# USB_UART.net
KiCad netlist of a schematic drawn in Altium Designer
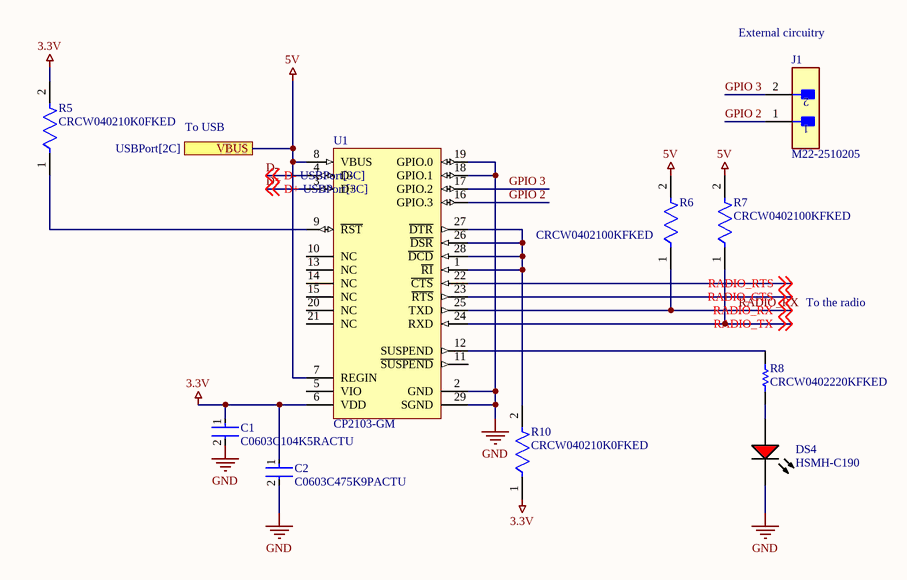
[diagram p0: USB_UART.SchDoc]

(export (version "E")
  (design (tool "Eeschema 10.0.6"))
  (components
    (comp (ref "C1")
      (value "C0603C104K5RACTU")
      (footprint "FP-C0603C-CF-MFG")
      (description "CAP CER 0.1UF 50V X7R 0603")
      (fields (field (name "TOLERANCE") "0.1") (field (name "MANUFACTURER") "KEMET"))
      (libsource (lib "Altium Content Vault") (part "b4654b650e69147ec39a6b967a45e02"))
    )
    (comp (ref "C2")
      (value "C0603C475K9PACTU")
      (footprint "FP-C0603-CG-MFG")
      (description "CAP CER 4.7UF 6.3V X5R 0603")
      (fields (field (name "TOLERANCE") "10%") (field (name "MANUFACTURER") "Kemet"))
      (libsource (lib "Altium Content Vault") (part "11868f565c42a9108669ba33697ecf6"))
    )
    (comp (ref "DS4")
      (value "HSMH-C190")
      (footprint "AVAG-HSMX-C190_V")
      (description "LED Uni-Color Red, 65 mW, 20 mA, -40 to 85 degC, 2-Pin SMD, RoHS, Tape and Reel")
      (libsource (lib "Altium Content Vault") (part "LED-RED-AK-2"))
    )
    (comp (ref "J1")
      (value "M22-2510205")
      (footprint "FP-M22-2510205-MFG")
      (description "CONN HEADER VERT 2POS 2MM")
      (fields
        (field (name "MANUFACTURER") "Harwin")
        (field (name "OCTOPART") "https://octopart.com/m22-2510205-harwin-2538221")
      )
      (libsource (lib "Altium Content Vault") (part "3bc925449376181038e59eaffc5286c"))
    )
    (comp (ref "R5")
      (value "CRCW040210K0FKED")
      (footprint "FP-CRCW0402-e3-IPC_B")
      (description "RES SMD 10K OHM 1% 1/16W 0402")
      (fields (field (name "TOLERANCE") "1%"))
      (libsource (lib "Altium Content Vault") (part "1029c3af85768c4190bb7ad29bc67b5"))
    )
    (comp (ref "R6")
      (value "CRCW0402100KFKED")
      (footprint "FP-CRCW0402-e3-IPC_C")
      (description "RES Thick Film, 100kΩ, 1%, 0.063W, 100ppm/°C, 0402")
      (fields (field (name "TOLERANCE") "1%"))
      (libsource (lib "Altium Content Vault") (part "1029c3af85768c4190bb7ad29bc67b5"))
    )
    (comp (ref "R7")
      (value "CRCW0402100KFKED")
      (footprint "FP-CRCW0402-e3-IPC_C")
      (description "RES Thick Film, 100kΩ, 1%, 0.063W, 100ppm/°C, 0402")
      (fields (field (name "TOLERANCE") "1%"))
      (libsource (lib "Altium Content Vault") (part "1029c3af85768c4190bb7ad29bc67b5"))
    )
    (comp (ref "R8")
      (value "CRCW0402220KFKED")
      (footprint "RESC1005X40X25LL05T05")
      (fields (field (name "MANUFACTURER") "Vishay Dale"))
      (libsource (lib "Altium Content Vault") (part "RES"))
    )
    (comp (ref "R10")
      (value "CRCW040210K0FKED")
      (footprint "FP-CRCW0402-e3-IPC_B")
      (description "RES SMD 10K OHM 1% 1/16W 0402")
      (fields (field (name "TOLERANCE") "1%"))
      (libsource (lib "Altium Content Vault") (part "1029c3af85768c4190bb7ad29bc67b5"))
    )
    (comp (ref "U1")
      (value "CP2103-GM")
      (footprint "SLAB-QFN-28-3125x3125TP_A_M")
      (description "Single-Chip USB to UART Bridge, 1024 Bytes EEPROM, -40 to 85 degC, 28-pin QFN, Tube")
      (fields (field (name "MANUFACTURER") "Silicon Labs"))
      (libsource (lib "Altium Content Vault") (part "SLAB-CP2103-QFN-28-29"))
    )
  )
  (nets
    (net (code "1") (name "/GPIO 2") (class "Default")
      (node (ref "J1") (pin "1") (pinfunction "1_1") (pintype "passive"))
      (node (ref "U1") (pin "16") (pinfunction "GPIO.3_16") (pintype "bidirectional"))
    )
    (net (code "2") (name "/GPIO 3") (class "Default")
      (node (ref "J1") (pin "2") (pinfunction "2_2") (pintype "passive"))
      (node (ref "U1") (pin "17") (pinfunction "GPIO.2_17") (pintype "bidirectional"))
    )
    (net (code "3") (name "3.3V") (class "Default")
      (node (ref "C1") (pin "1") (pinfunction "1_1") (pintype "passive"))
      (node (ref "C2") (pin "1") (pinfunction "1_1") (pintype "passive"))
      (node (ref "R10") (pin "1") (pinfunction "1_1") (pintype "passive"))
      (node (ref "R5") (pin "2") (pinfunction "2_2") (pintype "passive"))
      (node (ref "U1") (pin "6") (pinfunction "VDD_6") (pintype "power_in"))
    )
    (net (code "4") (name "5V") (class "Default")
      (node (ref "R6") (pin "2") (pinfunction "2_2") (pintype "passive"))
      (node (ref "R7") (pin "2") (pinfunction "2_2") (pintype "passive"))
      (node (ref "U1") (pin "7") (pinfunction "REGIN_7") (pintype "power_in"))
      (node (ref "U1") (pin "8") (pinfunction "VBUS_8") (pintype "input"))
    )
    (net (code "5") (name "D+") (class "Default")
      (node (ref "U1") (pin "3") (pinfunction "D+_3") (pintype "bidirectional"))
    )
    (net (code "6") (name "D-") (class "Default")
      (node (ref "U1") (pin "4") (pinfunction "D-_4") (pintype "bidirectional"))
    )
    (net (code "7") (name "GND") (class "Default")
      (node (ref "C1") (pin "2") (pinfunction "2_2") (pintype "passive"))
      (node (ref "C2") (pin "2") (pinfunction "2_2") (pintype "passive"))
      (node (ref "DS4") (pin "2") (pinfunction "K_2") (pintype "passive"))
      (node (ref "U1") (pin "18") (pinfunction "GPIO.1_18") (pintype "bidirectional"))
      (node (ref "U1") (pin "19") (pinfunction "GPIO.0_19") (pintype "bidirectional"))
      (node (ref "U1") (pin "2") (pinfunction "GND_2") (pintype "power_in"))
      (node (ref "U1") (pin "29") (pinfunction "SGND_29") (pintype "power_in"))
    )
    (net (code "8") (name "Net-(DS4-A)") (class "Default")
      (node (ref "DS4") (pin "1") (pinfunction "A_1") (pintype "passive"))
      (node (ref "R8") (pin "1") (pinfunction "1_1") (pintype "passive"))
    )
    (net (code "9") (name "Net-(U1-SUSPEND)") (class "Default")
      (node (ref "R8") (pin "2") (pinfunction "2_2") (pintype "passive"))
      (node (ref "U1") (pin "12") (pinfunction "SUSPEND_12") (pintype "output"))
    )
    (net (code "10") (name "Net-(U1-~{DCD})") (class "Default")
      (node (ref "R10") (pin "2") (pinfunction "2_2") (pintype "passive"))
      (node (ref "U1") (pin "1") (pinfunction "~{RI}_1") (pintype "input"))
      (node (ref "U1") (pin "26") (pinfunction "~{DSR}_26") (pintype "input"))
      (node (ref "U1") (pin "27") (pinfunction "~{DTR}_27") (pintype "output"))
      (node (ref "U1") (pin "28") (pinfunction "~{DCD}_28") (pintype "input"))
    )
    (net (code "11") (name "Net-(U1-~{RST})") (class "Default")
      (node (ref "R5") (pin "1") (pinfunction "1_1") (pintype "passive"))
      (node (ref "U1") (pin "9") (pinfunction "~{RST}_9") (pintype "bidirectional"))
    )
    (net (code "12") (name "RADIO_CTS") (class "Default")
      (node (ref "U1") (pin "23") (pinfunction "~{RTS}_23") (pintype "output"))
    )
    (net (code "13") (name "RADIO_RTS") (class "Default")
      (node (ref "U1") (pin "22") (pinfunction "~{CTS}_22") (pintype "input"))
    )
    (net (code "14") (name "RADIO_RX") (class "Default")
      (node (ref "R6") (pin "1") (pinfunction "1_1") (pintype "passive"))
      (node (ref "U1") (pin "25") (pinfunction "TXD_25") (pintype "output"))
    )
    (net (code "15") (name "RADIO_TX") (class "Default")
      (node (ref "R7") (pin "1") (pinfunction "1_1") (pintype "passive"))
      (node (ref "U1") (pin "24") (pinfunction "RXD_24") (pintype "input"))
    )
    (net (code "16") (name "unconnected-(U1-NC-Pad10)") (class "Default")
      (node (ref "U1") (pin "10") (pinfunction "NC_10") (pintype "passive"))
    )
    (net (code "17") (name "unconnected-(U1-NC-Pad13)") (class "Default")
      (node (ref "U1") (pin "13") (pinfunction "NC_13") (pintype "passive"))
    )
    (net (code "18") (name "unconnected-(U1-NC-Pad14)") (class "Default")
      (node (ref "U1") (pin "14") (pinfunction "NC_14") (pintype "passive"))
    )
    (net (code "19") (name "unconnected-(U1-NC-Pad15)") (class "Default")
      (node (ref "U1") (pin "15") (pinfunction "NC_15") (pintype "passive"))
    )
    (net (code "20") (name "unconnected-(U1-NC-Pad20)") (class "Default")
      (node (ref "U1") (pin "20") (pinfunction "NC_20") (pintype "passive"))
    )
    (net (code "21") (name "unconnected-(U1-NC-Pad21)") (class "Default")
      (node (ref "U1") (pin "21") (pinfunction "NC_21") (pintype "passive"))
    )
    (net (code "22") (name "unconnected-(U1-VIO-Pad5)") (class "Default")
      (node (ref "U1") (pin "5") (pinfunction "VIO_5") (pintype "power_in"))
    )
    (net (code "23") (name "unconnected-(U1-~{SUSPEND}-Pad11)") (class "Default")
      (node (ref "U1") (pin "11") (pinfunction "~{SUSPEND}_11") (pintype "output"))
    )
  )
)
